# Programmer.net
KiCad netlist of a schematic drawn in Altium Designer
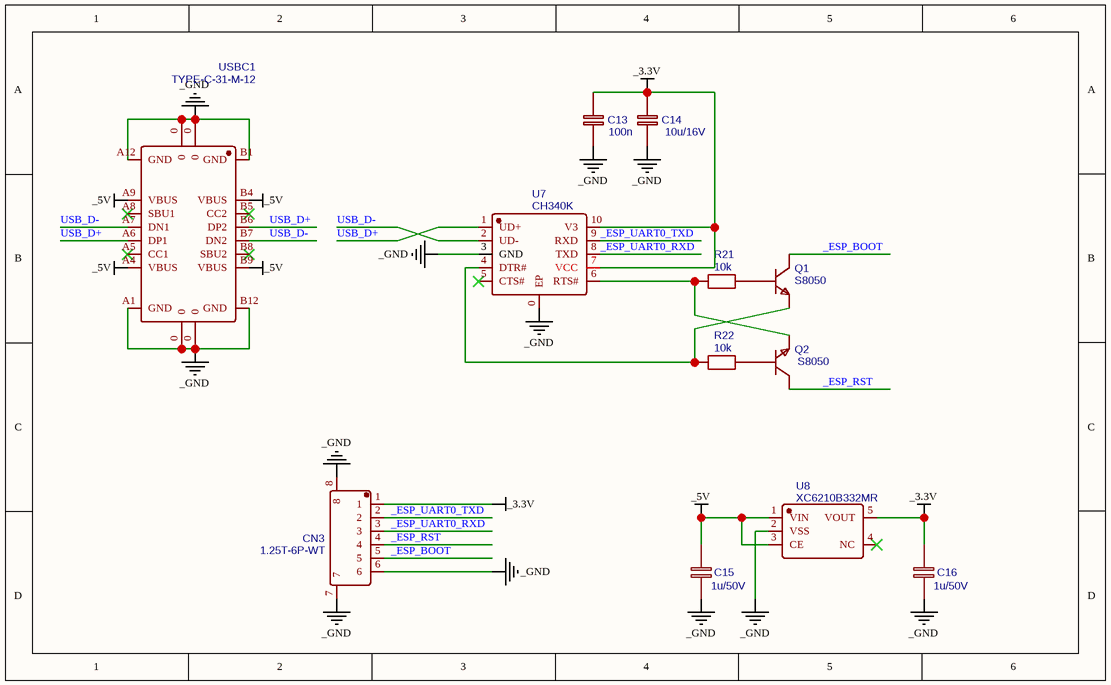
[diagram p0: Programmer.schdoc]

(export (version "E")
  (design (tool "Eeschema 10.0.6"))
  (components
    (comp (ref "C13")
      (value "100n")
      (fields
        (field (name "BOM_MANUFACTURER PART") "CC0603KRX7R9BB104")
        (field (name "BOM_SUPPLIER PART") "C14663")
      )
      (libsource (lib "altium-import") (part "root_0_100n_"))
    )
    (comp (ref "C14")
      (value "10u/16V")
      (fields
        (field (name "BOM_MANUFACTURER PART") "CL10A106KP8NNNC")
        (field (name "BOM_SUPPLIER PART") "C19702")
      )
      (libsource (lib "altium-import") (part "root_0_10u/16V_"))
    )
    (comp (ref "C15")
      (value "1u/50V")
      (fields
        (field (name "BOM_SUPPLIER PART") "C15849")
        (field (name "BOM_MANUFACTURER PART") "CL10A105KB8NNNC")
        (field (name "CONTRIBUTOR") "LCEDA_Lib")
      )
      (libsource (lib "altium-import") (part "root_1_1u/50V_"))
    )
    (comp (ref "C16")
      (value "1u/50V")
      (fields
        (field (name "BOM_SUPPLIER PART") "C15849")
        (field (name "BOM_MANUFACTURER PART") "CL10A105KB8NNNC")
        (field (name "CONTRIBUTOR") "LCEDA_Lib")
      )
      (libsource (lib "altium-import") (part "root_1_1u/50V_"))
    )
    (comp (ref "CN3")
      (value "1.25T-6P-WT")
      (fields (field (name "BOM_SUPPLIER PART") "C97377"))
      (libsource (lib "altium-import") (part "root_0_1.25T-6P-WT_"))
    )
    (comp (ref "Q1")
      (value "S8050")
      (fields (field (name "BOM_SUPPLIER PART") "C2146") (field (name "CONTRIBUTOR") "立创EDA官方封装库"))
      (libsource (lib "altium-import") (part "root_0_S8050_"))
    )
    (comp (ref "Q2")
      (value "S8050")
      (fields (field (name "BOM_SUPPLIER PART") "C2146") (field (name "CONTRIBUTOR") "立创EDA官方封装库"))
      (libsource (lib "altium-import") (part "root_2_S8050_"))
    )
    (comp (ref "R21")
      (value "10k")
      (fields
        (field (name "BOM_SUPPLIER PART") "C25804")
        (field (name "BOM_MANUFACTURER PART") "0603WAF1002T5E")
        (field (name "CONTRIBUTOR") "LCEDA_Lib")
      )
      (libsource (lib "altium-import") (part "root_2_10k_"))
    )
    (comp (ref "R22")
      (value "10k")
      (fields
        (field (name "BOM_SUPPLIER PART") "C25804")
        (field (name "BOM_MANUFACTURER PART") "0603WAF1002T5E")
        (field (name "CONTRIBUTOR") "LCEDA_Lib")
      )
      (libsource (lib "altium-import") (part "root_2_10k_"))
    )
    (comp (ref "U7")
      (value "CH340K")
      (fields (field (name "CONTRIBUTOR") "矛盾聚合体"))
      (libsource (lib "altium-import") (part "root_0_CH340K_"))
    )
    (comp (ref "U8")
      (value "XC6210B332MR")
      (fields (field (name "BOM_SUPPLIER PART") "C424705") (field (name "CONTRIBUTOR") "LCSC"))
      (libsource (lib "altium-import") (part "root_0_XC6210B332MR_"))
    )
    (comp (ref "USBC1")
      (value "TYPE-C-31-M-12")
      (fields (field (name "BOM_SUPPLIER PART") "C165948") (field (name "CONTRIBUTOR") "LCSC"))
      (libsource (lib "altium-import") (part "root_0_TYPE-C-31-M-12_"))
    )
  )
  (nets
    (net (code "1") (name "/USB_D+") (class "Default")
      (node (ref "U7") (pin "1") (pinfunction "UD+_1") (pintype "passive"))
      (node (ref "USBC1") (pin "A6") (pinfunction "DP1_A6") (pintype "passive"))
      (node (ref "USBC1") (pin "B6") (pinfunction "DP2_B6") (pintype "passive"))
    )
    (net (code "2") (name "/USB_D-") (class "Default")
      (node (ref "U7") (pin "2") (pinfunction "UD-_2") (pintype "passive"))
      (node (ref "USBC1") (pin "A7") (pinfunction "DN1_A7") (pintype "passive"))
      (node (ref "USBC1") (pin "B7") (pinfunction "DN2_B7") (pintype "passive"))
    )
    (net (code "3") (name "/_ESP_BOOT") (class "Default")
      (node (ref "CN3") (pin "5") (pinfunction "5_5") (pintype "passive"))
      (node (ref "Q1") (pin "3") (pinfunction "C_3") (pintype "passive"))
    )
    (net (code "4") (name "/_ESP_RST") (class "Default")
      (node (ref "CN3") (pin "4") (pinfunction "4_4") (pintype "passive"))
      (node (ref "Q2") (pin "3") (pinfunction "C_3") (pintype "passive"))
    )
    (net (code "5") (name "/_ESP_UART0_RXD") (class "Default")
      (node (ref "CN3") (pin "3") (pinfunction "3_3") (pintype "passive"))
      (node (ref "U7") (pin "8") (pinfunction "TXD_8") (pintype "passive"))
    )
    (net (code "6") (name "/_ESP_UART0_TXD") (class "Default")
      (node (ref "CN3") (pin "2") (pinfunction "2_2") (pintype "passive"))
      (node (ref "U7") (pin "9") (pinfunction "RXD_9") (pintype "passive"))
    )
    (net (code "7") (name "Net-(Q1-B)") (class "Default")
      (node (ref "Q1") (pin "1") (pinfunction "B_1") (pintype "passive"))
      (node (ref "R21") (pin "1") (pinfunction "1_1") (pintype "passive"))
    )
    (net (code "8") (name "Net-(Q1-E)") (class "Default")
      (node (ref "Q1") (pin "2") (pinfunction "E_2") (pintype "passive"))
      (node (ref "R22") (pin "2") (pinfunction "2_2") (pintype "passive"))
      (node (ref "U7") (pin "4") (pinfunction "DTR#_4") (pintype "passive"))
    )
    (net (code "9") (name "Net-(Q2-B)") (class "Default")
      (node (ref "Q2") (pin "1") (pinfunction "B_1") (pintype "passive"))
      (node (ref "R22") (pin "1") (pinfunction "1_1") (pintype "passive"))
    )
    (net (code "10") (name "Net-(Q2-E)") (class "Default")
      (node (ref "Q2") (pin "2") (pinfunction "E_2") (pintype "passive"))
      (node (ref "R21") (pin "2") (pinfunction "2_2") (pintype "passive"))
      (node (ref "U7") (pin "6") (pinfunction "RTS#_6") (pintype "passive"))
    )
    (net (code "11") (name "_3.3V") (class "Default")
      (node (ref "C13") (pin "2") (pinfunction "2_2") (pintype "passive"))
      (node (ref "C14") (pin "2") (pinfunction "2_2") (pintype "passive"))
      (node (ref "C16") (pin "2") (pinfunction "2_2") (pintype "passive"))
      (node (ref "CN3") (pin "1") (pinfunction "1_1") (pintype "passive"))
      (node (ref "U7") (pin "10") (pinfunction "V3_10") (pintype "passive"))
      (node (ref "U7") (pin "7") (pinfunction "VCC_7") (pintype "passive"))
      (node (ref "U8") (pin "5") (pinfunction "VOUT_5") (pintype "passive"))
    )
    (net (code "12") (name "_5V") (class "Default")
      (node (ref "C15") (pin "2") (pinfunction "2_2") (pintype "passive"))
      (node (ref "U8") (pin "1") (pinfunction "VIN_1") (pintype "passive"))
      (node (ref "U8") (pin "3") (pinfunction "CE_3") (pintype "passive"))
      (node (ref "USBC1") (pin "A4") (pinfunction "VBUS_A4") (pintype "passive"))
      (node (ref "USBC1") (pin "A9") (pinfunction "VBUS_A9") (pintype "passive"))
      (node (ref "USBC1") (pin "B4") (pinfunction "VBUS_B4") (pintype "passive"))
      (node (ref "USBC1") (pin "B9") (pinfunction "VBUS_B9") (pintype "passive"))
    )
    (net (code "13") (name "_GND") (class "Default")
      (node (ref "C13") (pin "1") (pinfunction "1_1") (pintype "passive"))
      (node (ref "C14") (pin "1") (pinfunction "1_1") (pintype "passive"))
      (node (ref "C15") (pin "1") (pinfunction "1_1") (pintype "passive"))
      (node (ref "C16") (pin "1") (pinfunction "1_1") (pintype "passive"))
      (node (ref "CN3") (pin "6") (pinfunction "6_6") (pintype "passive"))
      (node (ref "CN3") (pin "7") (pinfunction "7_7") (pintype "passive"))
      (node (ref "CN3") (pin "8") (pinfunction "8_8") (pintype "passive"))
      (node (ref "U7") (pin "0") (pinfunction "EP_0") (pintype "passive"))
      (node (ref "U7") (pin "3") (pinfunction "GND_3") (pintype "passive"))
      (node (ref "U8") (pin "2") (pinfunction "VSS_2") (pintype "passive"))
      (node (ref "USBC1") (pin "0") (pinfunction "0_0") (pintype "passive"))
      (node (ref "USBC1") (pin "A1") (pinfunction "GND_A1") (pintype "passive"))
      (node (ref "USBC1") (pin "A12") (pinfunction "GND_A12") (pintype "passive"))
      (node (ref "USBC1") (pin "B1") (pinfunction "GND_B1") (pintype "passive"))
      (node (ref "USBC1") (pin "B12") (pinfunction "GND_B12") (pintype "passive"))
    )
    (net (code "14") (name "unconnected-(U7-CTS#-Pad5)") (class "Default")
      (node (ref "U7") (pin "5") (pinfunction "CTS#_5") (pintype "passive+no_connect"))
    )
    (net (code "15") (name "unconnected-(U8-NC-Pad4)") (class "Default")
      (node (ref "U8") (pin "4") (pinfunction "NC_4") (pintype "passive+no_connect"))
    )
    (net (code "16") (name "unconnected-(USBC1-CC1-PadA5)") (class "Default")
      (node (ref "USBC1") (pin "A5") (pinfunction "CC1_A5") (pintype "passive+no_connect"))
    )
    (net (code "17") (name "unconnected-(USBC1-CC2-PadB5)") (class "Default")
      (node (ref "USBC1") (pin "B5") (pinfunction "CC2_B5") (pintype "passive+no_connect"))
    )
    (net (code "18") (name "unconnected-(USBC1-SBU1-PadA8)") (class "Default")
      (node (ref "USBC1") (pin "A8") (pinfunction "SBU1_A8") (pintype "passive+no_connect"))
    )
    (net (code "19") (name "unconnected-(USBC1-SBU2-PadB8)") (class "Default")
      (node (ref "USBC1") (pin "B8") (pinfunction "SBU2_B8") (pintype "passive+no_connect"))
    )
  )
)
